# FIT_HDMI_X22-18.net
KiCad netlist of a schematic drawn in Altium Designer
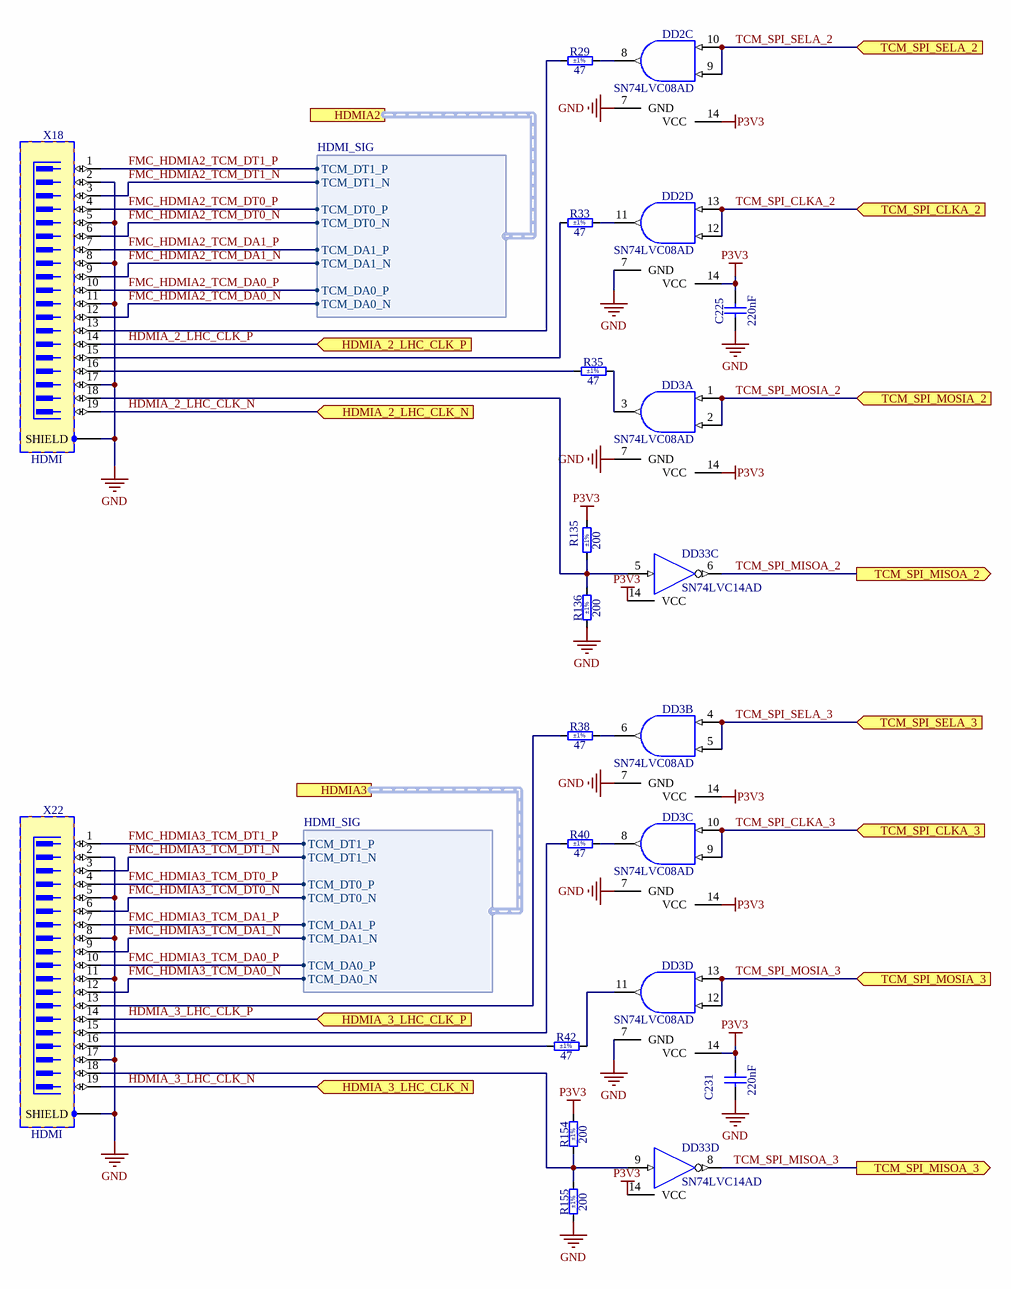
[diagram p0: FIT_HDMI_X22-18.SchDoc]

(export (version "E")
  (design (tool "Eeschema 10.0.6"))
  (components
    (comp (ref "C225")
      (value "220nF")
      (footprint "CAPC2012X135N")
      (description "Non-polarised capacitor")
      (fields
        (field (name "PART NUMBER") "CC0805_220NF_50V_10%_X7R")
        (field (name "VOLTAGE") "50V")
        (field (name "AUTHOR") "CERN DEM JLC")
      )
      (libsource (lib "Capacitors") (part "Capacitor - non polarized"))
    )
    (comp (ref "C231")
      (value "220nF")
      (footprint "CAPC2012X135N")
      (description "Non-polarised capacitor")
      (fields
        (field (name "PART NUMBER") "CC0805_220NF_50V_10%_X7R")
        (field (name "VOLTAGE") "50V")
        (field (name "AUTHOR") "CERN DEM JLC")
      )
      (libsource (lib "Capacitors") (part "Capacitor - non polarized"))
    )
    (comp (ref "DD2")
      (value "SN74LVC08AD")
      (footprint "SOIC127P600X175-14N")
      (description "Quad 2-Input AND Gate")
      (fields (field (name "MANUFACTURER") "TEXAS INSTRUMENTS") (field (name "AUTHOR") "CERN DEM JLC"))
      (libsource (lib "ICs And Semiconductors") (part "7408"))
    )
    (comp (ref "DD3")
      (value "SN74LVC08AD")
      (footprint "SOIC127P600X175-14N")
      (description "Quad 2-Input AND Gate")
      (fields (field (name "MANUFACTURER") "TEXAS INSTRUMENTS") (field (name "AUTHOR") "CERN DEM JLC"))
      (libsource (lib "ICs And Semiconductors") (part "7408"))
    )
    (comp (ref "DD33")
      (value "SN74LVC14AD")
      (footprint "SOIC127P600X175-14N")
      (description "Hex Schmitt-Trigger Inverter")
      (fields (field (name "MANUFACTURER") "TEXAS INSTRUMENTS") (field (name "AUTHOR") "CERN DEM JMW"))
      (libsource (lib "ICs And Semiconductors") (part "7414"))
    )
    (comp (ref "R29")
      (value "47")
      (footprint "RESC2012X60N")
      (description "Resistor - 1%")
      (fields
        (field (name "TOLERANCE") "±1%")
        (field (name "PART NUMBER") "R0805_47R_1%_0.125W_100PPM")
        (field (name "POWER") "0.125W")
        (field (name "AUTHOR") "CERN DEM JLC")
      )
      (libsource (lib "Resistors") (part "Resistor - 1%"))
    )
    (comp (ref "R33")
      (value "47")
      (footprint "RESC2012X60N")
      (description "Resistor - 1%")
      (fields
        (field (name "TOLERANCE") "±1%")
        (field (name "PART NUMBER") "R0805_47R_1%_0.125W_100PPM")
        (field (name "POWER") "0.125W")
        (field (name "AUTHOR") "CERN DEM JLC")
      )
      (libsource (lib "Resistors") (part "Resistor - 1%"))
    )
    (comp (ref "R35")
      (value "47")
      (footprint "RESC2012X60N")
      (description "Resistor - 1%")
      (fields
        (field (name "TOLERANCE") "±1%")
        (field (name "PART NUMBER") "R0805_47R_1%_0.125W_100PPM")
        (field (name "POWER") "0.125W")
        (field (name "AUTHOR") "CERN DEM JLC")
      )
      (libsource (lib "Resistors") (part "Resistor - 1%"))
    )
    (comp (ref "R38")
      (value "47")
      (footprint "RESC2012X60N")
      (description "Resistor - 1%")
      (fields
        (field (name "TOLERANCE") "±1%")
        (field (name "PART NUMBER") "R0805_47R_1%_0.125W_100PPM")
        (field (name "POWER") "0.125W")
        (field (name "AUTHOR") "CERN DEM JLC")
      )
      (libsource (lib "Resistors") (part "Resistor - 1%"))
    )
    (comp (ref "R40")
      (value "47")
      (footprint "RESC2012X60N")
      (description "Resistor - 1%")
      (fields
        (field (name "TOLERANCE") "±1%")
        (field (name "PART NUMBER") "R0805_47R_1%_0.125W_100PPM")
        (field (name "POWER") "0.125W")
        (field (name "AUTHOR") "CERN DEM JLC")
      )
      (libsource (lib "Resistors") (part "Resistor - 1%"))
    )
    (comp (ref "R42")
      (value "47")
      (footprint "RESC2012X60N")
      (description "Resistor - 1%")
      (fields
        (field (name "TOLERANCE") "±1%")
        (field (name "PART NUMBER") "R0805_47R_1%_0.125W_100PPM")
        (field (name "POWER") "0.125W")
        (field (name "AUTHOR") "CERN DEM JLC")
      )
      (libsource (lib "Resistors") (part "Resistor - 1%"))
    )
    (comp (ref "R135")
      (value "200")
      (footprint "RESC2012X60N")
      (description "Resistor - 1%")
      (fields
        (field (name "TOLERANCE") "±1%")
        (field (name "PART NUMBER") "R0805_200R_1%_0.125W_100PPM")
        (field (name "POWER") "0.125W")
        (field (name "AUTHOR") "CERN DEM JLC")
      )
      (libsource (lib "Resistors") (part "Resistor - 1%"))
    )
    (comp (ref "R136")
      (value "200")
      (footprint "RESC2012X60N")
      (description "Resistor - 1%")
      (fields
        (field (name "TOLERANCE") "±1%")
        (field (name "PART NUMBER") "R0805_200R_1%_0.125W_100PPM")
        (field (name "POWER") "0.125W")
        (field (name "AUTHOR") "CERN DEM JLC")
      )
      (libsource (lib "Resistors") (part "Resistor - 1%"))
    )
    (comp (ref "R154")
      (value "200")
      (footprint "RESC2012X60N")
      (description "Resistor - 1%")
      (fields
        (field (name "TOLERANCE") "±1%")
        (field (name "PART NUMBER") "R0805_200R_1%_0.125W_100PPM")
        (field (name "POWER") "0.125W")
        (field (name "AUTHOR") "CERN DEM JLC")
      )
      (libsource (lib "Resistors") (part "Resistor - 1%"))
    )
    (comp (ref "R155")
      (value "200")
      (footprint "RESC2012X60N")
      (description "Resistor - 1%")
      (fields
        (field (name "TOLERANCE") "±1%")
        (field (name "PART NUMBER") "R0805_200R_1%_0.125W_100PPM")
        (field (name "POWER") "0.125W")
        (field (name "AUTHOR") "CERN DEM JLC")
      )
      (libsource (lib "Resistors") (part "Resistor - 1%"))
    )
    (comp (ref "X18")
      (value "HDMI")
      (footprint "TYCO_2007435-1")
      (description "Connector HDMI 19 Male + 1 Shield")
      (fields
        (field (name "PART NUMBER") "TYCO_2007435-1")
        (field (name "MANUFACTURER") "TYCO ELECTRONICS")
        (field (name "AUTHOR") "CERN DEM MR")
      )
      (libsource (lib "Connectors") (part "Connector HDMI 19 Male + 1 Shield"))
    )
    (comp (ref "X22")
      (value "HDMI")
      (footprint "TYCO_2007435-1")
      (description "Connector HDMI 19 Male + 1 Shield")
      (fields
        (field (name "PART NUMBER") "TYCO_2007435-1")
        (field (name "MANUFACTURER") "TYCO ELECTRONICS")
        (field (name "AUTHOR") "CERN DEM MR")
      )
      (libsource (lib "Connectors") (part "Connector HDMI 19 Male + 1 Shield"))
    )
  )
  (nets
    (net (code "2") (name "/FMC_HDMIA2_TCM_DA0_N") (class "Default")
      (node (ref "X18") (pin "12") (pinfunction "12_12") (pintype "bidirectional"))
    )
    (net (code "3") (name "/FMC_HDMIA2_TCM_DA0_P") (class "Default")
      (node (ref "X18") (pin "10") (pinfunction "10_10") (pintype "bidirectional"))
    )
    (net (code "4") (name "/FMC_HDMIA2_TCM_DA1_N") (class "Default")
      (node (ref "X18") (pin "9") (pinfunction "9_9") (pintype "bidirectional"))
    )
    (net (code "5") (name "/FMC_HDMIA2_TCM_DA1_P") (class "Default")
      (node (ref "X18") (pin "7") (pinfunction "7_7") (pintype "bidirectional"))
    )
    (net (code "6") (name "/FMC_HDMIA2_TCM_DT0_N") (class "Default")
      (node (ref "X18") (pin "6") (pinfunction "6_6") (pintype "bidirectional"))
    )
    (net (code "7") (name "/FMC_HDMIA2_TCM_DT0_P") (class "Default")
      (node (ref "X18") (pin "4") (pinfunction "4_4") (pintype "bidirectional"))
    )
    (net (code "8") (name "/FMC_HDMIA2_TCM_DT1_N") (class "Default")
      (node (ref "X18") (pin "3") (pinfunction "3_3") (pintype "bidirectional"))
    )
    (net (code "9") (name "/FMC_HDMIA2_TCM_DT1_P") (class "Default")
      (node (ref "X18") (pin "1") (pinfunction "1_1") (pintype "bidirectional"))
    )
    (net (code "10") (name "/FMC_HDMIA3_TCM_DA0_N") (class "Default")
      (node (ref "X22") (pin "12") (pinfunction "12_12") (pintype "bidirectional"))
    )
    (net (code "11") (name "/FMC_HDMIA3_TCM_DA0_P") (class "Default")
      (node (ref "X22") (pin "10") (pinfunction "10_10") (pintype "bidirectional"))
    )
    (net (code "12") (name "/FMC_HDMIA3_TCM_DA1_N") (class "Default")
      (node (ref "X22") (pin "9") (pinfunction "9_9") (pintype "bidirectional"))
    )
    (net (code "13") (name "/FMC_HDMIA3_TCM_DA1_P") (class "Default")
      (node (ref "X22") (pin "7") (pinfunction "7_7") (pintype "bidirectional"))
    )
    (net (code "14") (name "/FMC_HDMIA3_TCM_DT0_N") (class "Default")
      (node (ref "X22") (pin "6") (pinfunction "6_6") (pintype "bidirectional"))
    )
    (net (code "15") (name "/FMC_HDMIA3_TCM_DT0_P") (class "Default")
      (node (ref "X22") (pin "4") (pinfunction "4_4") (pintype "bidirectional"))
    )
    (net (code "16") (name "/FMC_HDMIA3_TCM_DT1_N") (class "Default")
      (node (ref "X22") (pin "3") (pinfunction "3_3") (pintype "bidirectional"))
    )
    (net (code "17") (name "/FMC_HDMIA3_TCM_DT1_P") (class "Default")
      (node (ref "X22") (pin "1") (pinfunction "1_1") (pintype "bidirectional"))
    )
    (net (code "18") (name "/HDMIA_2_LHC_CLK_N") (class "Default")
      (node (ref "X18") (pin "19") (pinfunction "19_19") (pintype "bidirectional"))
    )
    (net (code "19") (name "/HDMIA_2_LHC_CLK_P") (class "Default")
      (node (ref "X18") (pin "14") (pinfunction "14_14") (pintype "bidirectional"))
    )
    (net (code "20") (name "/HDMIA_3_LHC_CLK_N") (class "Default")
      (node (ref "X22") (pin "19") (pinfunction "19_19") (pintype "bidirectional"))
    )
    (net (code "21") (name "/HDMIA_3_LHC_CLK_P") (class "Default")
      (node (ref "X22") (pin "14") (pinfunction "14_14") (pintype "bidirectional"))
    )
    (net (code "22") (name "/TCM_SPI_CLKA_2") (class "Default")
      (node (ref "DD2") (pin "12") (pinfunction "B_12") (pintype "input"))
      (node (ref "DD2") (pin "13") (pinfunction "A_13") (pintype "input"))
    )
    (net (code "23") (name "/TCM_SPI_CLKA_3") (class "Default")
      (node (ref "DD3") (pin "10") (pinfunction "A_10") (pintype "input"))
      (node (ref "DD3") (pin "9") (pinfunction "B_9") (pintype "input"))
    )
    (net (code "24") (name "/TCM_SPI_MISOA_2") (class "Default")
      (node (ref "DD33") (pin "6") (pinfunction "OUT_6") (pintype "output"))
    )
    (net (code "25") (name "/TCM_SPI_MISOA_3") (class "Default")
      (node (ref "DD33") (pin "8") (pinfunction "OUT_8") (pintype "output"))
    )
    (net (code "26") (name "/TCM_SPI_MOSIA_2") (class "Default")
      (node (ref "DD3") (pin "1") (pinfunction "A_1") (pintype "input"))
      (node (ref "DD3") (pin "2") (pinfunction "B_2") (pintype "input"))
    )
    (net (code "27") (name "/TCM_SPI_MOSIA_3") (class "Default")
      (node (ref "DD3") (pin "12") (pinfunction "B_12") (pintype "input"))
      (node (ref "DD3") (pin "13") (pinfunction "A_13") (pintype "input"))
    )
    (net (code "28") (name "/TCM_SPI_SELA_2") (class "Default")
      (node (ref "DD2") (pin "10") (pinfunction "A_10") (pintype "input"))
      (node (ref "DD2") (pin "9") (pinfunction "B_9") (pintype "input"))
    )
    (net (code "29") (name "/TCM_SPI_SELA_3") (class "Default")
      (node (ref "DD3") (pin "4") (pinfunction "A_4") (pintype "input"))
      (node (ref "DD3") (pin "5") (pinfunction "B_5") (pintype "input"))
    )
    (net (code "31") (name "GND") (class "Default")
      (node (ref "C225") (pin "1") (pinfunction "1_1") (pintype "passive"))
      (node (ref "C231") (pin "1") (pinfunction "1_1") (pintype "passive"))
      (node (ref "DD2") (pin "7") (pinfunction "GND_7") (pintype "power_in"))
      (node (ref "DD3") (pin "7") (pinfunction "GND_7") (pintype "power_in"))
      (node (ref "DD33") (pin "7") (pinfunction "GND_7") (pintype "power_in"))
      (node (ref "R136") (pin "1") (pinfunction "1_1") (pintype "passive"))
      (node (ref "R155") (pin "1") (pinfunction "1_1") (pintype "passive"))
      (node (ref "X18") (pin "11") (pinfunction "11_11") (pintype "bidirectional"))
      (node (ref "X18") (pin "17") (pinfunction "17_17") (pintype "bidirectional"))
      (node (ref "X18") (pin "2") (pinfunction "2_2") (pintype "bidirectional"))
      (node (ref "X18") (pin "5") (pinfunction "5_5") (pintype "bidirectional"))
      (node (ref "X18") (pin "8") (pinfunction "8_8") (pintype "bidirectional"))
      (node (ref "X18") (pin "SHIELD") (pinfunction "SHIELD_SHIELD") (pintype "power_in"))
      (node (ref "X22") (pin "11") (pinfunction "11_11") (pintype "bidirectional"))
      (node (ref "X22") (pin "17") (pinfunction "17_17") (pintype "bidirectional"))
      (node (ref "X22") (pin "2") (pinfunction "2_2") (pintype "bidirectional"))
      (node (ref "X22") (pin "5") (pinfunction "5_5") (pintype "bidirectional"))
      (node (ref "X22") (pin "8") (pinfunction "8_8") (pintype "bidirectional"))
      (node (ref "X22") (pin "SHIELD") (pinfunction "SHIELD_SHIELD") (pintype "power_in"))
    )
    (net (code "32") (name "Net-(DD2C-Y)") (class "Default")
      (node (ref "DD2") (pin "8") (pinfunction "Y_8") (pintype "output"))
      (node (ref "R29") (pin "2") (pinfunction "2_2") (pintype "passive"))
    )
    (net (code "33") (name "Net-(DD2D-Y)") (class "Default")
      (node (ref "DD2") (pin "11") (pinfunction "Y_11") (pintype "output"))
      (node (ref "R33") (pin "2") (pinfunction "2_2") (pintype "passive"))
    )
    (net (code "34") (name "Net-(DD3A-Y)") (class "Default")
      (node (ref "DD3") (pin "3") (pinfunction "Y_3") (pintype "output"))
      (node (ref "R35") (pin "2") (pinfunction "2_2") (pintype "passive"))
    )
    (net (code "35") (name "Net-(DD3B-Y)") (class "Default")
      (node (ref "DD3") (pin "6") (pinfunction "Y_6") (pintype "output"))
      (node (ref "R38") (pin "2") (pinfunction "2_2") (pintype "passive"))
    )
    (net (code "36") (name "Net-(DD3C-Y)") (class "Default")
      (node (ref "DD3") (pin "8") (pinfunction "Y_8") (pintype "output"))
      (node (ref "R40") (pin "2") (pinfunction "2_2") (pintype "passive"))
    )
    (net (code "37") (name "Net-(DD3D-Y)") (class "Default")
      (node (ref "DD3") (pin "11") (pinfunction "Y_11") (pintype "output"))
      (node (ref "R42") (pin "2") (pinfunction "2_2") (pintype "passive"))
    )
    (net (code "38") (name "Net-(DD33C-IN)") (class "Default")
      (node (ref "DD33") (pin "5") (pinfunction "IN_5") (pintype "input"))
      (node (ref "R135") (pin "1") (pinfunction "1_1") (pintype "passive"))
      (node (ref "R136") (pin "2") (pinfunction "2_2") (pintype "passive"))
      (node (ref "X18") (pin "18") (pinfunction "18_18") (pintype "bidirectional"))
    )
    (net (code "39") (name "Net-(DD33D-IN)") (class "Default")
      (node (ref "DD33") (pin "9") (pinfunction "IN_9") (pintype "input"))
      (node (ref "R154") (pin "1") (pinfunction "1_1") (pintype "passive"))
      (node (ref "R155") (pin "2") (pinfunction "2_2") (pintype "passive"))
      (node (ref "X22") (pin "18") (pinfunction "18_18") (pintype "bidirectional"))
    )
    (net (code "40") (name "Net-(R29-Pad1)") (class "Default")
      (node (ref "R29") (pin "1") (pinfunction "1_1") (pintype "passive"))
      (node (ref "X18") (pin "13") (pinfunction "13_13") (pintype "bidirectional"))
    )
    (net (code "41") (name "Net-(R33-Pad1)") (class "Default")
      (node (ref "R33") (pin "1") (pinfunction "1_1") (pintype "passive"))
      (node (ref "X18") (pin "15") (pinfunction "15_15") (pintype "bidirectional"))
    )
    (net (code "42") (name "Net-(R35-Pad1)") (class "Default")
      (node (ref "R35") (pin "1") (pinfunction "1_1") (pintype "passive"))
      (node (ref "X18") (pin "16") (pinfunction "16_16") (pintype "bidirectional"))
    )
    (net (code "43") (name "Net-(R38-Pad1)") (class "Default")
      (node (ref "R38") (pin "1") (pinfunction "1_1") (pintype "passive"))
      (node (ref "X22") (pin "13") (pinfunction "13_13") (pintype "bidirectional"))
    )
    (net (code "44") (name "Net-(R40-Pad1)") (class "Default")
      (node (ref "R40") (pin "1") (pinfunction "1_1") (pintype "passive"))
      (node (ref "X22") (pin "15") (pinfunction "15_15") (pintype "bidirectional"))
    )
    (net (code "45") (name "Net-(R42-Pad1)") (class "Default")
      (node (ref "R42") (pin "1") (pinfunction "1_1") (pintype "passive"))
      (node (ref "X22") (pin "16") (pinfunction "16_16") (pintype "bidirectional"))
    )
    (net (code "46") (name "P3V3") (class "Default")
      (node (ref "C225") (pin "2") (pinfunction "2_2") (pintype "passive"))
      (node (ref "C231") (pin "2") (pinfunction "2_2") (pintype "passive"))
      (node (ref "DD2") (pin "14") (pinfunction "VCC_14") (pintype "power_in"))
      (node (ref "DD3") (pin "14") (pinfunction "VCC_14") (pintype "power_in"))
      (node (ref "DD33") (pin "14") (pinfunction "VCC_14") (pintype "power_in"))
      (node (ref "R135") (pin "2") (pinfunction "2_2") (pintype "passive"))
      (node (ref "R154") (pin "2") (pinfunction "2_2") (pintype "passive"))
    )
  )
)
